# copycat_mult.net
KiCad netlist of a schematic drawn in EAGLE
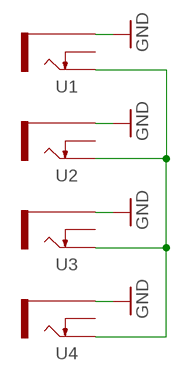
[diagram p0: schematic, sheet 1]

(export (version "E")
  (design (tool "Eeschema 10.0.6"))
  (components
    (comp (ref "U1")
      (value "THONKICONNNEW")
      (footprint "eagle-import:WQP-PJ301M-12_JACK")
      (libsource (lib "eagle-import") (part "THONKICONNNEW"))
    )
    (comp (ref "U2")
      (value "THONKICONNNEW")
      (footprint "eagle-import:WQP-PJ301M-12_JACK")
      (libsource (lib "eagle-import") (part "THONKICONNNEW"))
    )
    (comp (ref "U3")
      (value "THONKICONNNEW")
      (footprint "eagle-import:WQP-PJ301M-12_JACK")
      (libsource (lib "eagle-import") (part "THONKICONNNEW"))
    )
    (comp (ref "U4")
      (value "THONKICONNNEW")
      (footprint "eagle-import:WQP-PJ301M-12_JACK")
      (libsource (lib "eagle-import") (part "THONKICONNNEW"))
    )
  )
  (nets
    (net (code "1") (name "GND") (class "Default")
      (node (ref "U1") (pin "P$3_SLEEVE") (pinfunction "SLEEVE_P$3_SLEEVE") (pintype "passive"))
      (node (ref "U2") (pin "P$3_SLEEVE") (pinfunction "SLEEVE_P$3_SLEEVE") (pintype "passive"))
      (node (ref "U3") (pin "P$3_SLEEVE") (pinfunction "SLEEVE_P$3_SLEEVE") (pintype "passive"))
      (node (ref "U4") (pin "P$3_SLEEVE") (pinfunction "SLEEVE_P$3_SLEEVE") (pintype "passive"))
    )
    (net (code "2") (name "Net-(U1-TIP)") (class "Default")
      (node (ref "U1") (pin "P$1_TIP") (pinfunction "TIP_P$1_TIP") (pintype "passive"))
      (node (ref "U2") (pin "P$1_TIP") (pinfunction "TIP_P$1_TIP") (pintype "passive"))
      (node (ref "U3") (pin "P$1_TIP") (pinfunction "TIP_P$1_TIP") (pintype "passive"))
      (node (ref "U4") (pin "P$1_TIP") (pinfunction "TIP_P$1_TIP") (pintype "passive"))
    )
    (net (code "3") (name "unconnected-(U1-SWITCH-PadP$2_SWITCH)") (class "Default")
      (node (ref "U1") (pin "P$2_SWITCH") (pinfunction "SWITCH_P$2_SWITCH") (pintype "passive"))
    )
    (net (code "4") (name "unconnected-(U2-SWITCH-PadP$2_SWITCH)") (class "Default")
      (node (ref "U2") (pin "P$2_SWITCH") (pinfunction "SWITCH_P$2_SWITCH") (pintype "passive"))
    )
    (net (code "5") (name "unconnected-(U3-SWITCH-PadP$2_SWITCH)") (class "Default")
      (node (ref "U3") (pin "P$2_SWITCH") (pinfunction "SWITCH_P$2_SWITCH") (pintype "passive"))
    )
    (net (code "6") (name "unconnected-(U4-SWITCH-PadP$2_SWITCH)") (class "Default")
      (node (ref "U4") (pin "P$2_SWITCH") (pinfunction "SWITCH_P$2_SWITCH") (pintype "passive"))
    )
  )
)
